# MotorCtrl.net
KiCad netlist of a schematic drawn in Altium Designer
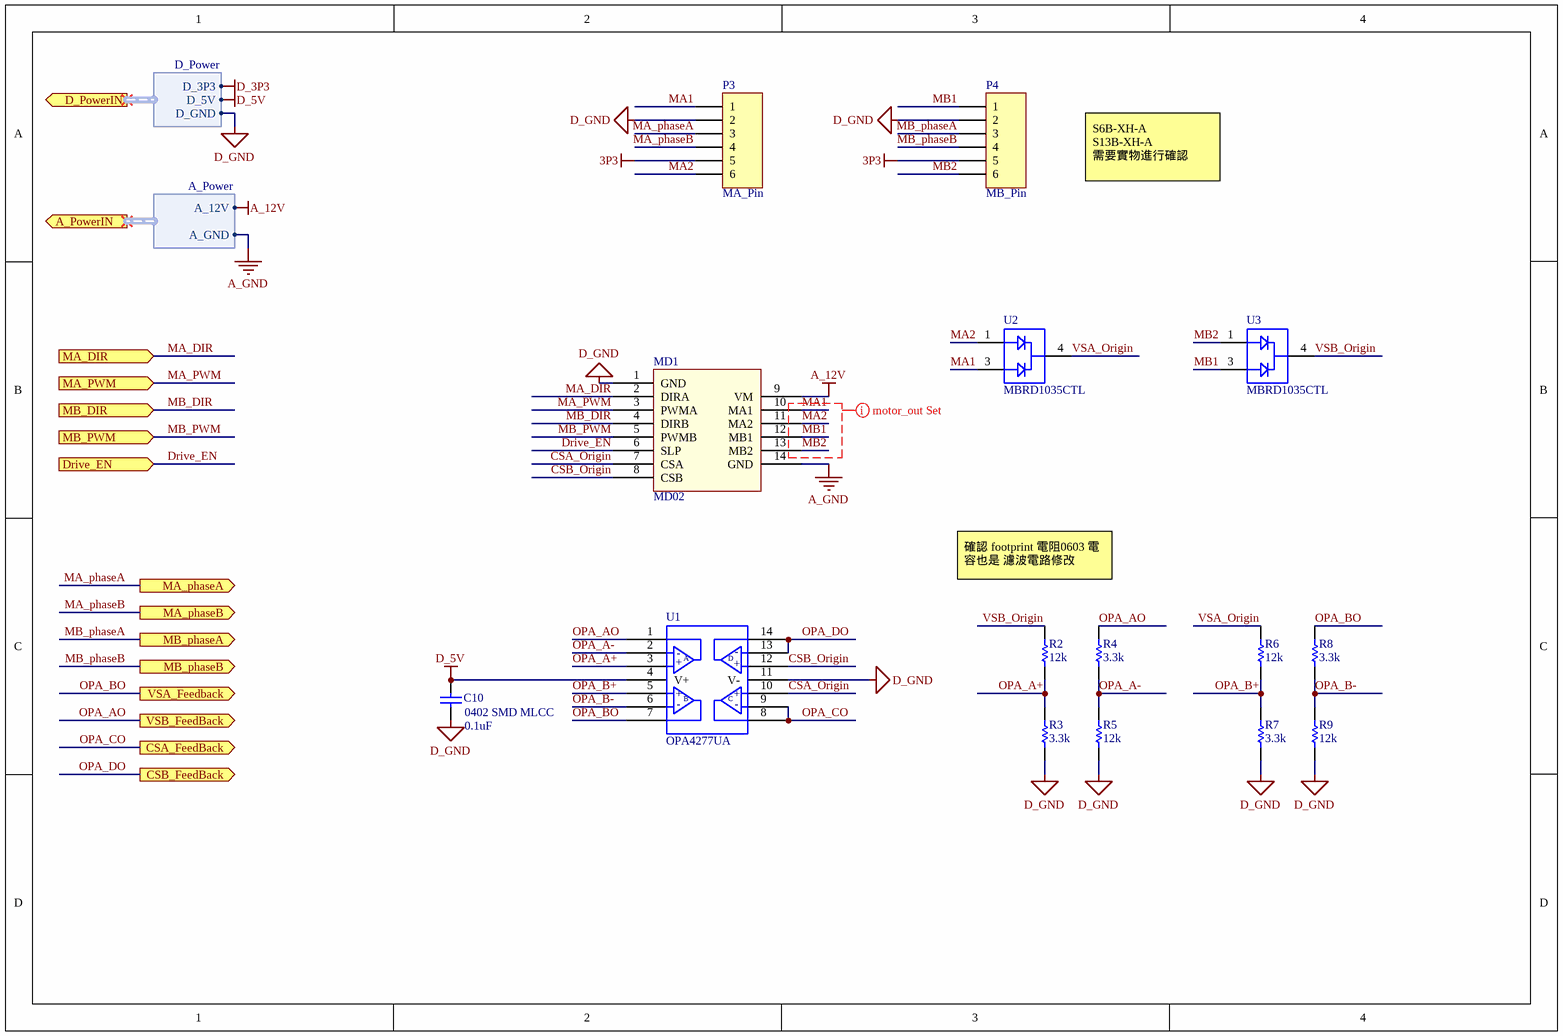
[diagram p0: MotorCtrl.SchDoc]

(export (version "E")
  (design (tool "Eeschema 10.0.6"))
  (components
    (comp (ref "C10")
      (value "0402 SMD MLCC")
      (footprint "0402")
      (description "Capacitor (Semiconductor SIM Model)")
      (fields (field (name "ALTIUM_VALUE") "0.1uF") (field (name "PUBLISHER") "Altium Limited"))
      (libsource (lib "Miscellaneous Devices") (part "Cap Semi"))
    )
    (comp (ref "MD1")
      (value "MD02")
      (footprint "OWMR:MOTOR_DRIVER")
      (description "17A 2 Cheel Motor Driver")
      (libsource (lib "OWMR") (part "Motor Driver"))
    )
    (comp (ref "P3")
      (value "MA_Pin")
      (footprint "OWMR:S6B-XH-A")
      (description "S6B-XH-A")
      (fields (field (name "PUBLISHER") "Altium Limited"))
      (libsource (lib "Miscellaneous Connectors") (part "Header 6"))
    )
    (comp (ref "P4")
      (value "MB_Pin")
      (footprint "OWMR:S6B-XH-A")
      (description "S6B-XH-A")
      (fields (field (name "PUBLISHER") "Altium Limited"))
      (libsource (lib "Miscellaneous Connectors") (part "Header 6"))
    )
    (comp (ref "R2")
      (value "12k")
      (footprint "OWMR:0402 SMD Res")
      (description "Resistor")
      (fields (field (name "PUBLISHER") "Altium Limited"))
      (libsource (lib "Miscellaneous Devices") (part "Res1"))
    )
    (comp (ref "R3")
      (value "3.3k")
      (footprint "OWMR:0402 SMD Res")
      (description "Resistor")
      (fields (field (name "PUBLISHER") "Altium Limited"))
      (libsource (lib "Miscellaneous Devices") (part "Res1"))
    )
    (comp (ref "R4")
      (value "3.3k")
      (footprint "OWMR:0402 SMD Res")
      (description "Resistor")
      (fields (field (name "PUBLISHER") "Altium Limited"))
      (libsource (lib "Miscellaneous Devices") (part "Res1"))
    )
    (comp (ref "R5")
      (value "12k")
      (footprint "OWMR:0402 SMD Res")
      (description "Resistor")
      (fields (field (name "PUBLISHER") "Altium Limited"))
      (libsource (lib "Miscellaneous Devices") (part "Res1"))
    )
    (comp (ref "R6")
      (value "12k")
      (footprint "OWMR:0402 SMD Res")
      (description "Resistor")
      (fields (field (name "PUBLISHER") "Altium Limited"))
      (libsource (lib "Miscellaneous Devices") (part "Res1"))
    )
    (comp (ref "R7")
      (value "3.3k")
      (footprint "OWMR:0402 SMD Res")
      (description "Resistor")
      (fields (field (name "PUBLISHER") "Altium Limited"))
      (libsource (lib "Miscellaneous Devices") (part "Res1"))
    )
    (comp (ref "R8")
      (value "3.3k")
      (footprint "OWMR:0402 SMD Res")
      (description "Resistor")
      (fields (field (name "PUBLISHER") "Altium Limited"))
      (libsource (lib "Miscellaneous Devices") (part "Res1"))
    )
    (comp (ref "R9")
      (value "12k")
      (footprint "OWMR:0402 SMD Res")
      (description "Resistor")
      (fields (field (name "PUBLISHER") "Altium Limited"))
      (libsource (lib "Miscellaneous Devices") (part "Res1"))
    )
    (comp (ref "U1")
      (value "OPA4277UA")
      (footprint "OWMR:OPA4277UA")
      (description "Small Signal Amplifier")
      (libsource (lib "OWMR") (part "Small Signal Amplifier"))
    )
    (comp (ref "U2")
      (value "MBRD1035CTL")
      (footprint "OWMR:MBRD1035CTL")
      (description "35V 10A 2 Cheel Diode")
      (libsource (lib "OWMR") (part "Diode IC"))
    )
    (comp (ref "U3")
      (value "MBRD1035CTL")
      (footprint "OWMR:MBRD1035CTL")
      (description "35V 10A 2 Cheel Diode")
      (libsource (lib "OWMR") (part "Diode IC"))
    )
  )
  (nets
    (net (code "3") (name "/CSA_Origin") (class "Default")
      (node (ref "MD1") (pin "7") (pinfunction "CSA_7") (pintype "passive"))
      (node (ref "U1") (pin "10") (pinfunction "+in_C_10") (pintype "passive"))
    )
    (net (code "4") (name "/CSB_Origin") (class "Default")
      (node (ref "MD1") (pin "8") (pinfunction "CSB_8") (pintype "passive"))
      (node (ref "U1") (pin "12") (pinfunction "+In_D_12") (pintype "passive"))
    )
    (net (code "5") (name "/Drive_EN") (class "Default")
      (node (ref "MD1") (pin "6") (pinfunction "SLP_6") (pintype "passive"))
    )
    (net (code "6") (name "/MA1") (class "Default")
      (node (ref "MD1") (pin "10") (pinfunction "MA1_10") (pintype "passive"))
      (node (ref "P3") (pin "1") (pinfunction "1_1") (pintype "passive"))
      (node (ref "U2") (pin "3") (pinfunction "3_3") (pintype "passive"))
    )
    (net (code "7") (name "/MA2") (class "Default")
      (node (ref "MD1") (pin "11") (pinfunction "MA2_11") (pintype "passive"))
      (node (ref "P3") (pin "6") (pinfunction "6_6") (pintype "passive"))
      (node (ref "U2") (pin "1") (pinfunction "1_1") (pintype "passive"))
    )
    (net (code "8") (name "/MA_DIR") (class "Default")
      (node (ref "MD1") (pin "2") (pinfunction "DIRA_2") (pintype "passive"))
    )
    (net (code "9") (name "/MA_PWM") (class "Default")
      (node (ref "MD1") (pin "3") (pinfunction "PWMA_3") (pintype "passive"))
    )
    (net (code "10") (name "/MA_phaseA") (class "Default")
      (node (ref "P3") (pin "3") (pinfunction "3_3") (pintype "passive"))
    )
    (net (code "11") (name "/MA_phaseB") (class "Default")
      (node (ref "P3") (pin "4") (pinfunction "4_4") (pintype "passive"))
    )
    (net (code "12") (name "/MB1") (class "Default")
      (node (ref "MD1") (pin "12") (pinfunction "MB1_12") (pintype "passive"))
      (node (ref "P4") (pin "1") (pinfunction "1_1") (pintype "passive"))
      (node (ref "U3") (pin "3") (pinfunction "3_3") (pintype "passive"))
    )
    (net (code "13") (name "/MB2") (class "Default")
      (node (ref "MD1") (pin "13") (pinfunction "MB2_13") (pintype "passive"))
      (node (ref "P4") (pin "6") (pinfunction "6_6") (pintype "passive"))
      (node (ref "U3") (pin "1") (pinfunction "1_1") (pintype "passive"))
    )
    (net (code "14") (name "/MB_DIR") (class "Default")
      (node (ref "MD1") (pin "4") (pinfunction "DIRB_4") (pintype "passive"))
    )
    (net (code "15") (name "/MB_PWM") (class "Default")
      (node (ref "MD1") (pin "5") (pinfunction "PWMB_5") (pintype "passive"))
    )
    (net (code "16") (name "/MB_phaseA") (class "Default")
      (node (ref "P4") (pin "3") (pinfunction "3_3") (pintype "passive"))
    )
    (net (code "17") (name "/MB_phaseB") (class "Default")
      (node (ref "P4") (pin "4") (pinfunction "4_4") (pintype "passive"))
    )
    (net (code "18") (name "/OPA_A+") (class "Default")
      (node (ref "R2") (pin "2") (pinfunction "2_2") (pintype "passive"))
      (node (ref "R3") (pin "1") (pinfunction "1_1") (pintype "passive"))
      (node (ref "U1") (pin "3") (pinfunction "+In_A_3") (pintype "passive"))
    )
    (net (code "19") (name "/OPA_A-") (class "Default")
      (node (ref "R4") (pin "1") (pinfunction "1_1") (pintype "passive"))
      (node (ref "R5") (pin "2") (pinfunction "2_2") (pintype "passive"))
      (node (ref "U1") (pin "2") (pinfunction "-In_A_2") (pintype "passive"))
    )
    (net (code "20") (name "/OPA_AO") (class "Default")
      (node (ref "R4") (pin "2") (pinfunction "2_2") (pintype "passive"))
      (node (ref "U1") (pin "1") (pinfunction "Out_A_1") (pintype "passive"))
    )
    (net (code "21") (name "/OPA_B+") (class "Default")
      (node (ref "R6") (pin "2") (pinfunction "2_2") (pintype "passive"))
      (node (ref "R7") (pin "1") (pinfunction "1_1") (pintype "passive"))
      (node (ref "U1") (pin "5") (pinfunction "+In_B_5") (pintype "passive"))
    )
    (net (code "22") (name "/OPA_B-") (class "Default")
      (node (ref "R8") (pin "1") (pinfunction "1_1") (pintype "passive"))
      (node (ref "R9") (pin "2") (pinfunction "2_2") (pintype "passive"))
      (node (ref "U1") (pin "6") (pinfunction "-In_B_6") (pintype "passive"))
    )
    (net (code "23") (name "/OPA_BO") (class "Default")
      (node (ref "R8") (pin "2") (pinfunction "2_2") (pintype "passive"))
      (node (ref "U1") (pin "7") (pinfunction "Out_B_7") (pintype "passive"))
    )
    (net (code "24") (name "/OPA_CO") (class "Default")
      (node (ref "U1") (pin "8") (pinfunction "Out_C_8") (pintype "passive"))
      (node (ref "U1") (pin "9") (pinfunction "-In_C_9") (pintype "passive"))
    )
    (net (code "25") (name "/OPA_DO") (class "Default")
      (node (ref "U1") (pin "13") (pinfunction "-In_D_13") (pintype "passive"))
      (node (ref "U1") (pin "14") (pinfunction "Out_D_14") (pintype "passive"))
    )
    (net (code "26") (name "/VSA_Origin") (class "Default")
      (node (ref "R6") (pin "1") (pinfunction "1_1") (pintype "passive"))
      (node (ref "U2") (pin "4") (pinfunction "4_4") (pintype "passive"))
    )
    (net (code "27") (name "/VSB_Origin") (class "Default")
      (node (ref "R2") (pin "1") (pinfunction "1_1") (pintype "passive"))
      (node (ref "U3") (pin "4") (pinfunction "4_4") (pintype "passive"))
    )
    (net (code "30") (name "3P3") (class "Default")
      (node (ref "P3") (pin "5") (pinfunction "5_5") (pintype "passive"))
      (node (ref "P4") (pin "5") (pinfunction "5_5") (pintype "passive"))
    )
    (net (code "31") (name "A_12V") (class "Default")
      (node (ref "MD1") (pin "9") (pinfunction "VM_9") (pintype "passive"))
    )
    (net (code "32") (name "A_GND") (class "Default")
      (node (ref "MD1") (pin "14") (pinfunction "GND_14") (pintype "passive"))
    )
    (net (code "34") (name "D_5V") (class "Default")
      (node (ref "C10") (pin "1") (pinfunction "1_1") (pintype "passive"))
      (node (ref "U1") (pin "4") (pinfunction "V+_4") (pintype "passive"))
    )
    (net (code "35") (name "D_GND") (class "Default")
      (node (ref "C10") (pin "2") (pinfunction "2_2") (pintype "passive"))
      (node (ref "MD1") (pin "1") (pinfunction "GND_1") (pintype "passive"))
      (node (ref "P3") (pin "2") (pinfunction "2_2") (pintype "passive"))
      (node (ref "P4") (pin "2") (pinfunction "2_2") (pintype "passive"))
      (node (ref "R3") (pin "2") (pinfunction "2_2") (pintype "passive"))
      (node (ref "R5") (pin "1") (pinfunction "1_1") (pintype "passive"))
      (node (ref "R7") (pin "2") (pinfunction "2_2") (pintype "passive"))
      (node (ref "R9") (pin "1") (pinfunction "1_1") (pintype "passive"))
      (node (ref "U1") (pin "11") (pinfunction "V-_11") (pintype "passive"))
    )
  )
)
